# CONNECT2.net
KiCad netlist of a schematic drawn in Altium Designer
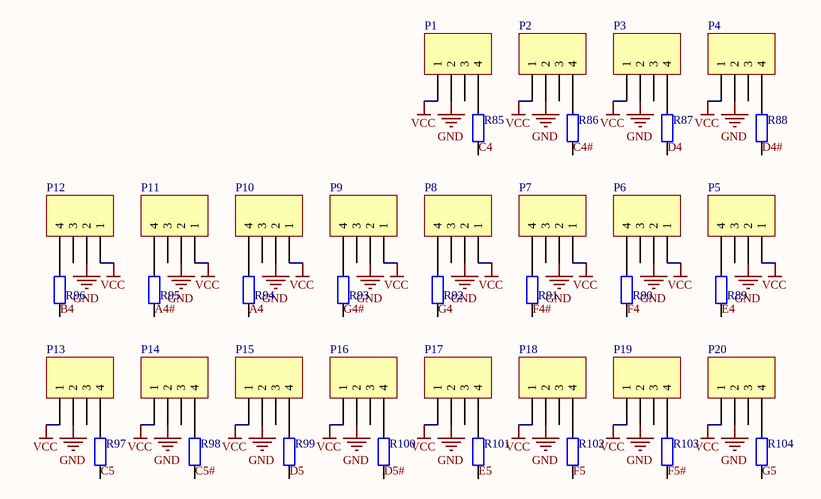
[diagram p0: CONNECT2.SchDoc]

(export (version "E")
  (design (tool "Eeschema 10.0.6"))
  (components
    (comp (ref "P1")
      (value "Header 4")
      (footprint "FPC1.0-2H-WS-4P")
      (description "Header, 4-Pin")
      (fields (field (name "PUBLISHER") "Altium Limited"))
      (libsource (lib "") (part "Header 4_1"))
    )
    (comp (ref "P2")
      (value "Header 4")
      (footprint "FPC1.0-2H-WS-4P")
      (description "Header, 4-Pin")
      (fields (field (name "PUBLISHER") "Altium Limited"))
      (libsource (lib "") (part "Header 4_1"))
    )
    (comp (ref "P3")
      (value "Header 4")
      (footprint "FPC1.0-2H-WS-4P")
      (description "Header, 4-Pin")
      (fields (field (name "PUBLISHER") "Altium Limited"))
      (libsource (lib "") (part "Header 4_1"))
    )
    (comp (ref "P4")
      (value "Header 4")
      (footprint "FPC1.0-2H-WS-4P")
      (description "Header, 4-Pin")
      (fields (field (name "PUBLISHER") "Altium Limited"))
      (libsource (lib "") (part "Header 4_1"))
    )
    (comp (ref "P5")
      (value "Header 4")
      (footprint "FPC1.0-2H-WS-4P")
      (description "Header, 4-Pin")
      (fields (field (name "PUBLISHER") "Altium Limited"))
      (libsource (lib "Miscellaneous Connectors") (part "Header 4"))
    )
    (comp (ref "P6")
      (value "Header 4")
      (footprint "FPC1.0-2H-WS-4P")
      (description "Header, 4-Pin")
      (fields (field (name "PUBLISHER") "Altium Limited"))
      (libsource (lib "Miscellaneous Connectors") (part "Header 4"))
    )
    (comp (ref "P7")
      (value "Header 4")
      (footprint "FPC1.0-2H-WS-4P")
      (description "Header, 4-Pin")
      (fields (field (name "PUBLISHER") "Altium Limited"))
      (libsource (lib "Miscellaneous Connectors") (part "Header 4"))
    )
    (comp (ref "P8")
      (value "Header 4")
      (footprint "FPC1.0-2H-WS-4P")
      (description "Header, 4-Pin")
      (fields (field (name "PUBLISHER") "Altium Limited"))
      (libsource (lib "Miscellaneous Connectors") (part "Header 4"))
    )
    (comp (ref "P9")
      (value "Header 4")
      (footprint "FPC1.0-2H-WS-4P")
      (description "Header, 4-Pin")
      (fields (field (name "PUBLISHER") "Altium Limited"))
      (libsource (lib "Miscellaneous Connectors") (part "Header 4"))
    )
    (comp (ref "P10")
      (value "Header 4")
      (footprint "FPC1.0-2H-WS-4P")
      (description "Header, 4-Pin")
      (fields (field (name "PUBLISHER") "Altium Limited"))
      (libsource (lib "Miscellaneous Connectors") (part "Header 4"))
    )
    (comp (ref "P11")
      (value "Header 4")
      (footprint "FPC1.0-2H-WS-4P")
      (description "Header, 4-Pin")
      (fields (field (name "PUBLISHER") "Altium Limited"))
      (libsource (lib "Miscellaneous Connectors") (part "Header 4"))
    )
    (comp (ref "P12")
      (value "Header 4")
      (footprint "FPC1.0-2H-WS-4P")
      (description "Header, 4-Pin")
      (fields (field (name "PUBLISHER") "Altium Limited"))
      (libsource (lib "Miscellaneous Connectors") (part "Header 4"))
    )
    (comp (ref "P13")
      (value "Header 4")
      (footprint "FPC1.0-2H-WS-4P")
      (description "Header, 4-Pin")
      (fields (field (name "PUBLISHER") "Altium Limited"))
      (libsource (lib "") (part "Header 4_1"))
    )
    (comp (ref "P14")
      (value "Header 4")
      (footprint "FPC1.0-2H-WS-4P")
      (description "Header, 4-Pin")
      (fields (field (name "PUBLISHER") "Altium Limited"))
      (libsource (lib "") (part "Header 4_1"))
    )
    (comp (ref "P15")
      (value "Header 4")
      (footprint "FPC1.0-2H-WS-4P")
      (description "Header, 4-Pin")
      (fields (field (name "PUBLISHER") "Altium Limited"))
      (libsource (lib "") (part "Header 4_1"))
    )
    (comp (ref "P16")
      (value "Header 4")
      (footprint "FPC1.0-2H-WS-4P")
      (description "Header, 4-Pin")
      (fields (field (name "PUBLISHER") "Altium Limited"))
      (libsource (lib "") (part "Header 4_1"))
    )
    (comp (ref "P17")
      (value "Header 4")
      (footprint "FPC1.0-2H-WS-4P")
      (description "Header, 4-Pin")
      (fields (field (name "PUBLISHER") "Altium Limited"))
      (libsource (lib "") (part "Header 4_1"))
    )
    (comp (ref "P18")
      (value "Header 4")
      (footprint "FPC1.0-2H-WS-4P")
      (description "Header, 4-Pin")
      (fields (field (name "PUBLISHER") "Altium Limited"))
      (libsource (lib "") (part "Header 4_1"))
    )
    (comp (ref "P19")
      (value "Header 4")
      (footprint "FPC1.0-2H-WS-4P")
      (description "Header, 4-Pin")
      (fields (field (name "PUBLISHER") "Altium Limited"))
      (libsource (lib "") (part "Header 4_1"))
    )
    (comp (ref "P20")
      (value "Header 4")
      (footprint "FPC1.0-2H-WS-4P")
      (description "Header, 4-Pin")
      (fields (field (name "PUBLISHER") "Altium Limited"))
      (libsource (lib "") (part "Header 4_1"))
    )
    (comp (ref "R85")
      (value "1KΩ (1001) ±1%")
      (footprint "0603_R")
      (description "贴片电阻")
      (libsource (lib "") (part "0603 1KΩ (1001) 1%_1"))
    )
    (comp (ref "R86")
      (value "1KΩ (1001) ±1%")
      (footprint "0603_R")
      (description "贴片电阻")
      (libsource (lib "") (part "0603 1KΩ (1001) 1%_1"))
    )
    (comp (ref "R87")
      (value "1KΩ (1001) ±1%")
      (footprint "0603_R")
      (description "贴片电阻")
      (libsource (lib "") (part "0603 1KΩ (1001) 1%_1"))
    )
    (comp (ref "R88")
      (value "1KΩ (1001) ±1%")
      (footprint "0603_R")
      (description "贴片电阻")
      (libsource (lib "") (part "0603 1KΩ (1001) 1%_1"))
    )
    (comp (ref "R89")
      (value "1KΩ (1001) ±1%")
      (footprint "0603_R")
      (description "贴片电阻")
      (libsource (lib "Miscellaneous Devices LC") (part "0603 1KΩ (1001) 1%"))
    )
    (comp (ref "R90")
      (value "1KΩ (1001) ±1%")
      (footprint "0603_R")
      (description "贴片电阻")
      (libsource (lib "Miscellaneous Devices LC") (part "0603 1KΩ (1001) 1%"))
    )
    (comp (ref "R91")
      (value "1KΩ (1001) ±1%")
      (footprint "0603_R")
      (description "贴片电阻")
      (libsource (lib "Miscellaneous Devices LC") (part "0603 1KΩ (1001) 1%"))
    )
    (comp (ref "R92")
      (value "1KΩ (1001) ±1%")
      (footprint "0603_R")
      (description "贴片电阻")
      (libsource (lib "Miscellaneous Devices LC") (part "0603 1KΩ (1001) 1%"))
    )
    (comp (ref "R93")
      (value "1KΩ (1001) ±1%")
      (footprint "0603_R")
      (description "贴片电阻")
      (libsource (lib "Miscellaneous Devices LC") (part "0603 1KΩ (1001) 1%"))
    )
    (comp (ref "R94")
      (value "1KΩ (1001) ±1%")
      (footprint "0603_R")
      (description "贴片电阻")
      (libsource (lib "Miscellaneous Devices LC") (part "0603 1KΩ (1001) 1%"))
    )
    (comp (ref "R95")
      (value "1KΩ (1001) ±1%")
      (footprint "0603_R")
      (description "贴片电阻")
      (libsource (lib "Miscellaneous Devices LC") (part "0603 1KΩ (1001) 1%"))
    )
    (comp (ref "R96")
      (value "1KΩ (1001) ±1%")
      (footprint "0603_R")
      (description "贴片电阻")
      (libsource (lib "Miscellaneous Devices LC") (part "0603 1KΩ (1001) 1%"))
    )
    (comp (ref "R97")
      (value "1KΩ (1001) ±1%")
      (footprint "0603_R")
      (description "贴片电阻")
      (libsource (lib "") (part "0603 1KΩ (1001) 1%_1"))
    )
    (comp (ref "R98")
      (value "1KΩ (1001) ±1%")
      (footprint "0603_R")
      (description "贴片电阻")
      (libsource (lib "") (part "0603 1KΩ (1001) 1%_1"))
    )
    (comp (ref "R99")
      (value "1KΩ (1001) ±1%")
      (footprint "0603_R")
      (description "贴片电阻")
      (libsource (lib "") (part "0603 1KΩ (1001) 1%_1"))
    )
    (comp (ref "R100")
      (value "1KΩ (1001) ±1%")
      (footprint "0603_R")
      (description "贴片电阻")
      (libsource (lib "") (part "0603 1KΩ (1001) 1%_1"))
    )
    (comp (ref "R101")
      (value "1KΩ (1001) ±1%")
      (footprint "0603_R")
      (description "贴片电阻")
      (libsource (lib "") (part "0603 1KΩ (1001) 1%_1"))
    )
    (comp (ref "R102")
      (value "1KΩ (1001) ±1%")
      (footprint "0603_R")
      (description "贴片电阻")
      (libsource (lib "") (part "0603 1KΩ (1001) 1%_1"))
    )
    (comp (ref "R103")
      (value "1KΩ (1001) ±1%")
      (footprint "0603_R")
      (description "贴片电阻")
      (libsource (lib "") (part "0603 1KΩ (1001) 1%_1"))
    )
    (comp (ref "R104")
      (value "1KΩ (1001) ±1%")
      (footprint "0603_R")
      (description "贴片电阻")
      (libsource (lib "") (part "0603 1KΩ (1001) 1%_1"))
    )
  )
  (nets
    (net (code "1") (name "/A4") (class "Default")
      (node (ref "R94") (pin "1") (pinfunction "1_1") (pintype "passive"))
    )
    (net (code "2") (name "/A4#") (class "Default")
      (node (ref "R95") (pin "1") (pinfunction "1_1") (pintype "passive"))
    )
    (net (code "3") (name "/B4") (class "Default")
      (node (ref "R96") (pin "1") (pinfunction "1_1") (pintype "passive"))
    )
    (net (code "4") (name "/C4") (class "Default")
      (node (ref "R85") (pin "1") (pinfunction "1_1") (pintype "passive"))
    )
    (net (code "5") (name "/C4#") (class "Default")
      (node (ref "R86") (pin "1") (pinfunction "1_1") (pintype "passive"))
    )
    (net (code "6") (name "/C5") (class "Default")
      (node (ref "R97") (pin "1") (pinfunction "1_1") (pintype "passive"))
    )
    (net (code "7") (name "/C5#") (class "Default")
      (node (ref "R98") (pin "1") (pinfunction "1_1") (pintype "passive"))
    )
    (net (code "8") (name "/D4") (class "Default")
      (node (ref "R87") (pin "1") (pinfunction "1_1") (pintype "passive"))
    )
    (net (code "9") (name "/D4#") (class "Default")
      (node (ref "R88") (pin "1") (pinfunction "1_1") (pintype "passive"))
    )
    (net (code "10") (name "/D5") (class "Default")
      (node (ref "R99") (pin "1") (pinfunction "1_1") (pintype "passive"))
    )
    (net (code "11") (name "/D5#") (class "Default")
      (node (ref "R100") (pin "1") (pinfunction "1_1") (pintype "passive"))
    )
    (net (code "12") (name "/E4") (class "Default")
      (node (ref "R89") (pin "1") (pinfunction "1_1") (pintype "passive"))
    )
    (net (code "13") (name "/E5") (class "Default")
      (node (ref "R101") (pin "1") (pinfunction "1_1") (pintype "passive"))
    )
    (net (code "14") (name "/F4") (class "Default")
      (node (ref "R90") (pin "1") (pinfunction "1_1") (pintype "passive"))
    )
    (net (code "15") (name "/F4#") (class "Default")
      (node (ref "R91") (pin "1") (pinfunction "1_1") (pintype "passive"))
    )
    (net (code "16") (name "/F5") (class "Default")
      (node (ref "R102") (pin "1") (pinfunction "1_1") (pintype "passive"))
    )
    (net (code "17") (name "/F5#") (class "Default")
      (node (ref "R103") (pin "1") (pinfunction "1_1") (pintype "passive"))
    )
    (net (code "18") (name "/G4") (class "Default")
      (node (ref "R92") (pin "1") (pinfunction "1_1") (pintype "passive"))
    )
    (net (code "19") (name "/G4#") (class "Default")
      (node (ref "R93") (pin "1") (pinfunction "1_1") (pintype "passive"))
    )
    (net (code "20") (name "/G5") (class "Default")
      (node (ref "R104") (pin "1") (pinfunction "1_1") (pintype "passive"))
    )
    (net (code "21") (name "GND") (class "Default")
      (node (ref "P1") (pin "2") (pinfunction "2_2") (pintype "passive"))
      (node (ref "P10") (pin "2") (pinfunction "2_2") (pintype "passive"))
      (node (ref "P11") (pin "2") (pinfunction "2_2") (pintype "passive"))
      (node (ref "P12") (pin "2") (pinfunction "2_2") (pintype "passive"))
      (node (ref "P13") (pin "2") (pinfunction "2_2") (pintype "passive"))
      (node (ref "P14") (pin "2") (pinfunction "2_2") (pintype "passive"))
      (node (ref "P15") (pin "2") (pinfunction "2_2") (pintype "passive"))
      (node (ref "P16") (pin "2") (pinfunction "2_2") (pintype "passive"))
      (node (ref "P17") (pin "2") (pinfunction "2_2") (pintype "passive"))
      (node (ref "P18") (pin "2") (pinfunction "2_2") (pintype "passive"))
      (node (ref "P19") (pin "2") (pinfunction "2_2") (pintype "passive"))
      (node (ref "P2") (pin "2") (pinfunction "2_2") (pintype "passive"))
      (node (ref "P20") (pin "2") (pinfunction "2_2") (pintype "passive"))
      (node (ref "P3") (pin "2") (pinfunction "2_2") (pintype "passive"))
      (node (ref "P4") (pin "2") (pinfunction "2_2") (pintype "passive"))
      (node (ref "P5") (pin "2") (pinfunction "2_2") (pintype "passive"))
      (node (ref "P6") (pin "2") (pinfunction "2_2") (pintype "passive"))
      (node (ref "P7") (pin "2") (pinfunction "2_2") (pintype "passive"))
      (node (ref "P8") (pin "2") (pinfunction "2_2") (pintype "passive"))
      (node (ref "P9") (pin "2") (pinfunction "2_2") (pintype "passive"))
    )
    (net (code "22") (name "Net-(P1-Pad4)") (class "Default")
      (node (ref "P1") (pin "4") (pinfunction "4_4") (pintype "passive"))
      (node (ref "R85") (pin "2") (pinfunction "2_2") (pintype "passive"))
    )
    (net (code "23") (name "Net-(P2-Pad4)") (class "Default")
      (node (ref "P2") (pin "4") (pinfunction "4_4") (pintype "passive"))
      (node (ref "R86") (pin "2") (pinfunction "2_2") (pintype "passive"))
    )
    (net (code "24") (name "Net-(P3-Pad4)") (class "Default")
      (node (ref "P3") (pin "4") (pinfunction "4_4") (pintype "passive"))
      (node (ref "R87") (pin "2") (pinfunction "2_2") (pintype "passive"))
    )
    (net (code "25") (name "Net-(P4-Pad4)") (class "Default")
      (node (ref "P4") (pin "4") (pinfunction "4_4") (pintype "passive"))
      (node (ref "R88") (pin "2") (pinfunction "2_2") (pintype "passive"))
    )
    (net (code "26") (name "Net-(P5-Pad4)") (class "Default")
      (node (ref "P5") (pin "4") (pinfunction "4_4") (pintype "passive"))
      (node (ref "R89") (pin "2") (pinfunction "2_2") (pintype "passive"))
    )
    (net (code "27") (name "Net-(P6-Pad4)") (class "Default")
      (node (ref "P6") (pin "4") (pinfunction "4_4") (pintype "passive"))
      (node (ref "R90") (pin "2") (pinfunction "2_2") (pintype "passive"))
    )
    (net (code "28") (name "Net-(P7-Pad4)") (class "Default")
      (node (ref "P7") (pin "4") (pinfunction "4_4") (pintype "passive"))
      (node (ref "R91") (pin "2") (pinfunction "2_2") (pintype "passive"))
    )
    (net (code "29") (name "Net-(P8-Pad4)") (class "Default")
      (node (ref "P8") (pin "4") (pinfunction "4_4") (pintype "passive"))
      (node (ref "R92") (pin "2") (pinfunction "2_2") (pintype "passive"))
    )
    (net (code "30") (name "Net-(P9-Pad4)") (class "Default")
      (node (ref "P9") (pin "4") (pinfunction "4_4") (pintype "passive"))
      (node (ref "R93") (pin "2") (pinfunction "2_2") (pintype "passive"))
    )
    (net (code "31") (name "Net-(P10-Pad4)") (class "Default")
      (node (ref "P10") (pin "4") (pinfunction "4_4") (pintype "passive"))
      (node (ref "R94") (pin "2") (pinfunction "2_2") (pintype "passive"))
    )
    (net (code "32") (name "Net-(P11-Pad4)") (class "Default")
      (node (ref "P11") (pin "4") (pinfunction "4_4") (pintype "passive"))
      (node (ref "R95") (pin "2") (pinfunction "2_2") (pintype "passive"))
    )
    (net (code "33") (name "Net-(P12-Pad4)") (class "Default")
      (node (ref "P12") (pin "4") (pinfunction "4_4") (pintype "passive"))
      (node (ref "R96") (pin "2") (pinfunction "2_2") (pintype "passive"))
    )
    (net (code "34") (name "Net-(P13-Pad4)") (class "Default")
      (node (ref "P13") (pin "4") (pinfunction "4_4") (pintype "passive"))
      (node (ref "R97") (pin "2") (pinfunction "2_2") (pintype "passive"))
    )
    (net (code "35") (name "Net-(P14-Pad4)") (class "Default")
      (node (ref "P14") (pin "4") (pinfunction "4_4") (pintype "passive"))
      (node (ref "R98") (pin "2") (pinfunction "2_2") (pintype "passive"))
    )
    (net (code "36") (name "Net-(P15-Pad4)") (class "Default")
      (node (ref "P15") (pin "4") (pinfunction "4_4") (pintype "passive"))
      (node (ref "R99") (pin "2") (pinfunction "2_2") (pintype "passive"))
    )
    (net (code "37") (name "Net-(P16-Pad4)") (class "Default")
      (node (ref "P16") (pin "4") (pinfunction "4_4") (pintype "passive"))
      (node (ref "R100") (pin "2") (pinfunction "2_2") (pintype "passive"))
    )
    (net (code "38") (name "Net-(P17-Pad4)") (class "Default")
      (node (ref "P17") (pin "4") (pinfunction "4_4") (pintype "passive"))
      (node (ref "R101") (pin "2") (pinfunction "2_2") (pintype "passive"))
    )
    (net (code "39") (name "Net-(P18-Pad4)") (class "Default")
      (node (ref "P18") (pin "4") (pinfunction "4_4") (pintype "passive"))
      (node (ref "R102") (pin "2") (pinfunction "2_2") (pintype "passive"))
    )
    (net (code "40") (name "Net-(P19-Pad4)") (class "Default")
      (node (ref "P19") (pin "4") (pinfunction "4_4") (pintype "passive"))
      (node (ref "R103") (pin "2") (pinfunction "2_2") (pintype "passive"))
    )
    (net (code "41") (name "Net-(P20-Pad4)") (class "Default")
      (node (ref "P20") (pin "4") (pinfunction "4_4") (pintype "passive"))
      (node (ref "R104") (pin "2") (pinfunction "2_2") (pintype "passive"))
    )
    (net (code "42") (name "VCC") (class "Default")
      (node (ref "P1") (pin "1") (pinfunction "1_1") (pintype "passive"))
      (node (ref "P10") (pin "1") (pinfunction "1_1") (pintype "passive"))
      (node (ref "P11") (pin "1") (pinfunction "1_1") (pintype "passive"))
      (node (ref "P12") (pin "1") (pinfunction "1_1") (pintype "passive"))
      (node (ref "P13") (pin "1") (pinfunction "1_1") (pintype "passive"))
      (node (ref "P14") (pin "1") (pinfunction "1_1") (pintype "passive"))
      (node (ref "P15") (pin "1") (pinfunction "1_1") (pintype "passive"))
      (node (ref "P16") (pin "1") (pinfunction "1_1") (pintype "passive"))
      (node (ref "P17") (pin "1") (pinfunction "1_1") (pintype "passive"))
      (node (ref "P18") (pin "1") (pinfunction "1_1") (pintype "passive"))
      (node (ref "P19") (pin "1") (pinfunction "1_1") (pintype "passive"))
      (node (ref "P2") (pin "1") (pinfunction "1_1") (pintype "passive"))
      (node (ref "P20") (pin "1") (pinfunction "1_1") (pintype "passive"))
      (node (ref "P3") (pin "1") (pinfunction "1_1") (pintype "passive"))
      (node (ref "P4") (pin "1") (pinfunction "1_1") (pintype "passive"))
      (node (ref "P5") (pin "1") (pinfunction "1_1") (pintype "passive"))
      (node (ref "P6") (pin "1") (pinfunction "1_1") (pintype "passive"))
      (node (ref "P7") (pin "1") (pinfunction "1_1") (pintype "passive"))
      (node (ref "P8") (pin "1") (pinfunction "1_1") (pintype "passive"))
      (node (ref "P9") (pin "1") (pinfunction "1_1") (pintype "passive"))
    )
    (net (code "43") (name "unconnected-(P1-Pad3)") (class "Default")
      (node (ref "P1") (pin "3") (pinfunction "3_3") (pintype "passive"))
    )
    (net (code "44") (name "unconnected-(P2-Pad3)") (class "Default")
      (node (ref "P2") (pin "3") (pinfunction "3_3") (pintype "passive"))
    )
    (net (code "45") (name "unconnected-(P3-Pad3)") (class "Default")
      (node (ref "P3") (pin "3") (pinfunction "3_3") (pintype "passive"))
    )
    (net (code "46") (name "unconnected-(P4-Pad3)") (class "Default")
      (node (ref "P4") (pin "3") (pinfunction "3_3") (pintype "passive"))
    )
    (net (code "47") (name "unconnected-(P5-Pad3)") (class "Default")
      (node (ref "P5") (pin "3") (pinfunction "3_3") (pintype "passive"))
    )
    (net (code "48") (name "unconnected-(P6-Pad3)") (class "Default")
      (node (ref "P6") (pin "3") (pinfunction "3_3") (pintype "passive"))
    )
    (net (code "49") (name "unconnected-(P7-Pad3)") (class "Default")
      (node (ref "P7") (pin "3") (pinfunction "3_3") (pintype "passive"))
    )
    (net (code "50") (name "unconnected-(P8-Pad3)") (class "Default")
      (node (ref "P8") (pin "3") (pinfunction "3_3") (pintype "passive"))
    )
    (net (code "51") (name "unconnected-(P9-Pad3)") (class "Default")
      (node (ref "P9") (pin "3") (pinfunction "3_3") (pintype "passive"))
    )
    (net (code "52") (name "unconnected-(P10-Pad3)") (class "Default")
      (node (ref "P10") (pin "3") (pinfunction "3_3") (pintype "passive"))
    )
    (net (code "53") (name "unconnected-(P11-Pad3)") (class "Default")
      (node (ref "P11") (pin "3") (pinfunction "3_3") (pintype "passive"))
    )
    (net (code "54") (name "unconnected-(P12-Pad3)") (class "Default")
      (node (ref "P12") (pin "3") (pinfunction "3_3") (pintype "passive"))
    )
    (net (code "55") (name "unconnected-(P13-Pad3)") (class "Default")
      (node (ref "P13") (pin "3") (pinfunction "3_3") (pintype "passive"))
    )
    (net (code "56") (name "unconnected-(P14-Pad3)") (class "Default")
      (node (ref "P14") (pin "3") (pinfunction "3_3") (pintype "passive"))
    )
    (net (code "57") (name "unconnected-(P15-Pad3)") (class "Default")
      (node (ref "P15") (pin "3") (pinfunction "3_3") (pintype "passive"))
    )
    (net (code "58") (name "unconnected-(P16-Pad3)") (class "Default")
      (node (ref "P16") (pin "3") (pinfunction "3_3") (pintype "passive"))
    )
    (net (code "59") (name "unconnected-(P17-Pad3)") (class "Default")
      (node (ref "P17") (pin "3") (pinfunction "3_3") (pintype "passive"))
    )
    (net (code "60") (name "unconnected-(P18-Pad3)") (class "Default")
      (node (ref "P18") (pin "3") (pinfunction "3_3") (pintype "passive"))
    )
    (net (code "61") (name "unconnected-(P19-Pad3)") (class "Default")
      (node (ref "P19") (pin "3") (pinfunction "3_3") (pintype "passive"))
    )
    (net (code "62") (name "unconnected-(P20-Pad3)") (class "Default")
      (node (ref "P20") (pin "3") (pinfunction "3_3") (pintype "passive"))
    )
  )
)
